# cs301_group7.net
KiCad netlist of a schematic drawn in Altium Designer
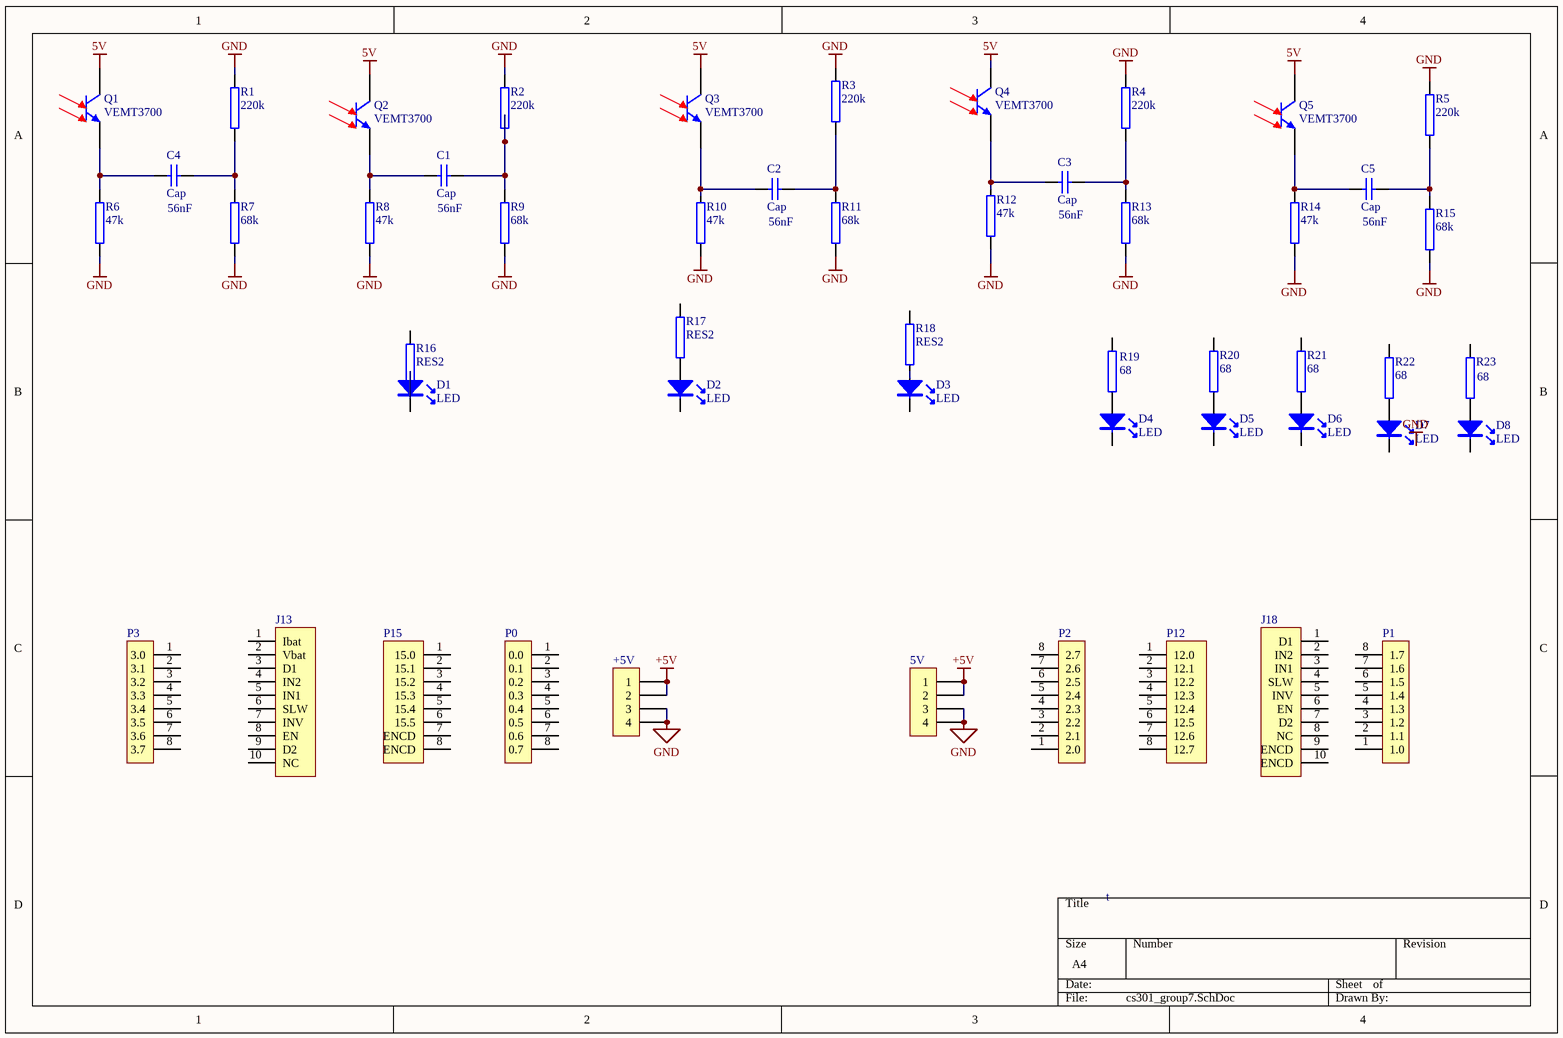
[diagram p0: cs301_group7.SchDoc]

(export (version "E")
  (design (tool "Eeschema 10.0.6"))
  (components
    (comp (ref "+5V")
      (value "5V")
      (footprint "IDC4")
      (description "Connector")
      (libsource (lib "Miscellaneous Devices") (part "CON4"))
    )
    (comp (ref "5V")
      (value "5V")
      (footprint "IDC4")
      (description "Connector")
      (libsource (lib "Miscellaneous Devices") (part "CON4"))
    )
    (comp (ref "C1")
      (value "Cap")
      (footprint "RAD-0.3")
      (description "Capacitor")
      (fields (field (name "ALTIUM_VALUE") "56nF") (field (name "PUBLISHER") "Altium Limited"))
      (libsource (lib "Miscellaneous Devices") (part "Cap"))
    )
    (comp (ref "C2")
      (value "Cap")
      (footprint "RAD-0.3")
      (description "Capacitor")
      (fields (field (name "ALTIUM_VALUE") "56nF") (field (name "PUBLISHER") "Altium Limited"))
      (libsource (lib "Miscellaneous Devices") (part "Cap"))
    )
    (comp (ref "C3")
      (value "Cap")
      (footprint "RAD-0.3")
      (description "Capacitor")
      (fields (field (name "ALTIUM_VALUE") "56nF") (field (name "PUBLISHER") "Altium Limited"))
      (libsource (lib "Miscellaneous Devices") (part "Cap"))
    )
    (comp (ref "C4")
      (value "Cap")
      (footprint "RAD-0.3")
      (description "Capacitor")
      (fields (field (name "ALTIUM_VALUE") "56nF") (field (name "PUBLISHER") "Altium Limited"))
      (libsource (lib "Miscellaneous Devices") (part "Cap"))
    )
    (comp (ref "C5")
      (value "Cap")
      (footprint "RAD-0.3")
      (description "Capacitor")
      (fields (field (name "ALTIUM_VALUE") "56nF") (field (name "PUBLISHER") "Altium Limited"))
      (libsource (lib "Miscellaneous Devices") (part "Cap"))
    )
    (comp (ref "D1") (value "LED") (footprint "LED0.1/5MM") (libsource (lib "COMSYS301_2013") (part "LED")))
    (comp (ref "D2") (value "LED") (footprint "LED0.1/5MM") (libsource (lib "COMSYS301_2013") (part "LED")))
    (comp (ref "D3") (value "LED") (footprint "LED0.1/5MM") (libsource (lib "COMSYS301_2013") (part "LED")))
    (comp (ref "D4") (value "LED") (footprint "LED0.1/5MM") (libsource (lib "COMSYS301_2013") (part "LED")))
    (comp (ref "D5") (value "LED") (footprint "LED0.1/5MM") (libsource (lib "COMSYS301_2013") (part "LED")))
    (comp (ref "D6") (value "LED") (footprint "LED0.1/5MM") (libsource (lib "COMSYS301_2013") (part "LED")))
    (comp (ref "D7") (value "LED") (footprint "LED0.1/5MM") (libsource (lib "COMSYS301_2013") (part "LED")))
    (comp (ref "D8") (value "LED") (footprint "LED0.1/5MM") (libsource (lib "COMSYS301_2013") (part "LED")))
    (comp (ref "J13")
      (value "CON10")
      (footprint "idc10")
      (description "Connector")
      (libsource (lib "") (part "CON10_1"))
    )
    (comp (ref "J18")
      (value "CON10")
      (footprint "IDC10")
      (description "Connector")
      (libsource (lib "Miscellaneous Devices") (part "CON10"))
    )
    (comp (ref "P0")
      (value "P0")
      (footprint "idc8")
      (description "Connector")
      (libsource (lib "Miscellaneous Devices") (part "CON8"))
    )
    (comp (ref "P1")
      (value "P1")
      (footprint "idc8")
      (description "Connector")
      (libsource (lib "") (part "CON8_1"))
    )
    (comp (ref "P2")
      (value "P2")
      (footprint "idc8")
      (description "Connector")
      (libsource (lib "") (part "CON8_2"))
    )
    (comp (ref "P3")
      (value "P3")
      (footprint "idc8")
      (description "Connector")
      (libsource (lib "Miscellaneous Devices") (part "CON8"))
    )
    (comp (ref "P12")
      (value "P12")
      (footprint "idc8")
      (description "Connector")
      (libsource (lib "Miscellaneous Devices") (part "CON8_1"))
    )
    (comp (ref "P15")
      (value "P15")
      (footprint "idc8")
      (description "Connector")
      (libsource (lib "") (part "CON8_1_1"))
    )
    (comp (ref "Q1")
      (value "VEMT3700")
      (footprint "VEMT3700")
      (description "Silicon NPN Phototransistor")
      (libsource (lib "COMSYS301_2013") (part "VEMT3700"))
    )
    (comp (ref "Q2")
      (value "VEMT3700")
      (footprint "VEMT3700")
      (description "Silicon NPN Phototransistor")
      (libsource (lib "COMSYS301_2013") (part "VEMT3700"))
    )
    (comp (ref "Q3")
      (value "VEMT3700")
      (footprint "VEMT3700")
      (description "Silicon NPN Phototransistor")
      (libsource (lib "COMSYS301_2013") (part "VEMT3700"))
    )
    (comp (ref "Q4")
      (value "VEMT3700")
      (footprint "VEMT3700")
      (description "Silicon NPN Phototransistor")
      (libsource (lib "COMSYS301_2013") (part "VEMT3700"))
    )
    (comp (ref "Q5")
      (value "VEMT3700")
      (footprint "VEMT3700")
      (description "Silicon NPN Phototransistor")
      (libsource (lib "COMSYS301_2013") (part "VEMT3700"))
    )
    (comp (ref "R1") (value "220k") (footprint "AXIAL0.4") (libsource (lib "COMSYS301_2013") (part "RES2")))
    (comp (ref "R2") (value "220k") (footprint "AXIAL0.4") (libsource (lib "COMSYS301_2013") (part "RES2")))
    (comp (ref "R3") (value "220k") (footprint "AXIAL0.4") (libsource (lib "COMSYS301_2013") (part "RES2")))
    (comp (ref "R4") (value "220k") (footprint "AXIAL0.4") (libsource (lib "COMSYS301_2013") (part "RES2")))
    (comp (ref "R5") (value "220k") (footprint "AXIAL0.4") (libsource (lib "COMSYS301_2013") (part "RES2")))
    (comp (ref "R6") (value "47k") (footprint "AXIAL0.4") (libsource (lib "COMSYS301_2013") (part "RES2")))
    (comp (ref "R7") (value "68k") (footprint "AXIAL0.4") (libsource (lib "COMSYS301_2013") (part "RES2")))
    (comp (ref "R8") (value "47k") (footprint "AXIAL0.4") (libsource (lib "COMSYS301_2013") (part "RES2")))
    (comp (ref "R9") (value "68k") (footprint "AXIAL0.4") (libsource (lib "COMSYS301_2013") (part "RES2")))
    (comp (ref "R10") (value "47k") (footprint "AXIAL0.4") (libsource (lib "COMSYS301_2013") (part "RES2")))
    (comp (ref "R11") (value "68k") (footprint "AXIAL0.4") (libsource (lib "COMSYS301_2013") (part "RES2")))
    (comp (ref "R12") (value "47k") (footprint "AXIAL0.4") (libsource (lib "COMSYS301_2013") (part "RES2")))
    (comp (ref "R13") (value "68k") (footprint "AXIAL0.4") (libsource (lib "COMSYS301_2013") (part "RES2")))
    (comp (ref "R14") (value "47k") (footprint "AXIAL0.4") (libsource (lib "COMSYS301_2013") (part "RES2")))
    (comp (ref "R15") (value "68k") (footprint "AXIAL0.4") (libsource (lib "COMSYS301_2013") (part "RES2")))
    (comp (ref "R16") (value "RES2") (footprint "AXIAL0.4") (libsource (lib "COMSYS301_2013") (part "RES2")))
    (comp (ref "R17") (value "RES2") (footprint "AXIAL0.4") (libsource (lib "COMSYS301_2013") (part "RES2")))
    (comp (ref "R18") (value "RES2") (footprint "AXIAL0.4") (libsource (lib "COMSYS301_2013") (part "RES2")))
    (comp (ref "R19") (value "68") (footprint "AXIAL0.4") (libsource (lib "COMSYS301_2013") (part "RES2")))
    (comp (ref "R20") (value "68") (footprint "AXIAL0.4") (libsource (lib "COMSYS301_2013") (part "RES2")))
    (comp (ref "R21") (value "68") (footprint "AXIAL0.4") (libsource (lib "COMSYS301_2013") (part "RES2")))
    (comp (ref "R22") (value "68") (footprint "AXIAL0.4") (libsource (lib "COMSYS301_2013") (part "RES2")))
    (comp (ref "R23") (value "68") (footprint "AXIAL0.4") (libsource (lib "COMSYS301_2013") (part "RES2")))
  )
  (nets
    (net (code "1") (name "+5V") (class "Default")
      (node (ref "+5V") (pin "1") (pinfunction "1_1") (pintype "passive"))
      (node (ref "+5V") (pin "2") (pinfunction "2_2") (pintype "passive"))
      (node (ref "5V") (pin "1") (pinfunction "1_1") (pintype "passive"))
      (node (ref "5V") (pin "2") (pinfunction "2_2") (pintype "passive"))
    )
    (net (code "2") (name "5V") (class "Default")
      (node (ref "Q1") (pin "1") (pinfunction "C_1") (pintype "passive"))
      (node (ref "Q2") (pin "1") (pinfunction "C_1") (pintype "passive"))
      (node (ref "Q3") (pin "1") (pinfunction "C_1") (pintype "passive"))
      (node (ref "Q4") (pin "1") (pinfunction "C_1") (pintype "passive"))
      (node (ref "Q5") (pin "1") (pinfunction "C_1") (pintype "passive"))
    )
    (net (code "3") (name "GND") (class "Default")
      (node (ref "+5V") (pin "3") (pinfunction "3_3") (pintype "passive"))
      (node (ref "+5V") (pin "4") (pinfunction "4_4") (pintype "passive"))
      (node (ref "5V") (pin "3") (pinfunction "3_3") (pintype "passive"))
      (node (ref "5V") (pin "4") (pinfunction "4_4") (pintype "passive"))
      (node (ref "R1") (pin "2") (pinfunction "2_2") (pintype "passive"))
      (node (ref "R10") (pin "1") (pinfunction "1_1") (pintype "passive"))
      (node (ref "R11") (pin "1") (pinfunction "1_1") (pintype "passive"))
      (node (ref "R12") (pin "1") (pinfunction "1_1") (pintype "passive"))
      (node (ref "R13") (pin "1") (pinfunction "1_1") (pintype "passive"))
      (node (ref "R14") (pin "1") (pinfunction "1_1") (pintype "passive"))
      (node (ref "R15") (pin "1") (pinfunction "1_1") (pintype "passive"))
      (node (ref "R2") (pin "2") (pinfunction "2_2") (pintype "passive"))
      (node (ref "R3") (pin "2") (pinfunction "2_2") (pintype "passive"))
      (node (ref "R4") (pin "2") (pinfunction "2_2") (pintype "passive"))
      (node (ref "R5") (pin "2") (pinfunction "2_2") (pintype "passive"))
      (node (ref "R6") (pin "1") (pinfunction "1_1") (pintype "passive"))
      (node (ref "R7") (pin "1") (pinfunction "1_1") (pintype "passive"))
      (node (ref "R8") (pin "1") (pinfunction "1_1") (pintype "passive"))
      (node (ref "R9") (pin "1") (pinfunction "1_1") (pintype "passive"))
    )
    (net (code "4") (name "Net-(C1-Pad2)") (class "Default")
      (node (ref "C1") (pin "2") (pinfunction "2_2") (pintype "passive"))
      (node (ref "R2") (pin "1") (pinfunction "1_1") (pintype "passive"))
      (node (ref "R9") (pin "2") (pinfunction "2_2") (pintype "passive"))
    )
    (net (code "5") (name "Net-(C2-Pad2)") (class "Default")
      (node (ref "C2") (pin "2") (pinfunction "2_2") (pintype "passive"))
      (node (ref "R11") (pin "2") (pinfunction "2_2") (pintype "passive"))
      (node (ref "R3") (pin "1") (pinfunction "1_1") (pintype "passive"))
    )
    (net (code "6") (name "Net-(C3-Pad2)") (class "Default")
      (node (ref "C3") (pin "2") (pinfunction "2_2") (pintype "passive"))
      (node (ref "R13") (pin "2") (pinfunction "2_2") (pintype "passive"))
      (node (ref "R4") (pin "1") (pinfunction "1_1") (pintype "passive"))
    )
    (net (code "7") (name "Net-(C4-Pad2)") (class "Default")
      (node (ref "C4") (pin "2") (pinfunction "2_2") (pintype "passive"))
      (node (ref "R1") (pin "1") (pinfunction "1_1") (pintype "passive"))
      (node (ref "R7") (pin "2") (pinfunction "2_2") (pintype "passive"))
    )
    (net (code "8") (name "Net-(C5-Pad2)") (class "Default")
      (node (ref "C5") (pin "2") (pinfunction "2_2") (pintype "passive"))
      (node (ref "R15") (pin "2") (pinfunction "2_2") (pintype "passive"))
      (node (ref "R5") (pin "1") (pinfunction "1_1") (pintype "passive"))
    )
    (net (code "9") (name "Net-(D1-1)") (class "Default")
      (node (ref "D1") (pin "A") (pinfunction "1_A") (pintype "passive"))
      (node (ref "R16") (pin "1") (pinfunction "1_1") (pintype "passive"))
    )
    (net (code "10") (name "Net-(D2-1)") (class "Default")
      (node (ref "D2") (pin "A") (pinfunction "1_A") (pintype "passive"))
      (node (ref "R17") (pin "1") (pinfunction "1_1") (pintype "passive"))
    )
    (net (code "11") (name "Net-(D3-1)") (class "Default")
      (node (ref "D3") (pin "A") (pinfunction "1_A") (pintype "passive"))
      (node (ref "R18") (pin "2") (pinfunction "2_2") (pintype "passive"))
    )
    (net (code "12") (name "Net-(D4-1)") (class "Default")
      (node (ref "D4") (pin "A") (pinfunction "1_A") (pintype "passive"))
      (node (ref "R19") (pin "1") (pinfunction "1_1") (pintype "passive"))
    )
    (net (code "13") (name "Net-(D5-1)") (class "Default")
      (node (ref "D5") (pin "A") (pinfunction "1_A") (pintype "passive"))
      (node (ref "R20") (pin "1") (pinfunction "1_1") (pintype "passive"))
    )
    (net (code "14") (name "Net-(D6-1)") (class "Default")
      (node (ref "D6") (pin "A") (pinfunction "1_A") (pintype "passive"))
      (node (ref "R21") (pin "1") (pinfunction "1_1") (pintype "passive"))
    )
    (net (code "15") (name "Net-(D7-1)") (class "Default")
      (node (ref "D7") (pin "A") (pinfunction "1_A") (pintype "passive"))
      (node (ref "R22") (pin "1") (pinfunction "1_1") (pintype "passive"))
    )
    (net (code "16") (name "Net-(D8-1)") (class "Default")
      (node (ref "D8") (pin "A") (pinfunction "1_A") (pintype "passive"))
      (node (ref "R23") (pin "1") (pinfunction "1_1") (pintype "passive"))
    )
    (net (code "17") (name "Net-(Q1-E)") (class "Default")
      (node (ref "C4") (pin "1") (pinfunction "1_1") (pintype "passive"))
      (node (ref "Q1") (pin "2") (pinfunction "E_2") (pintype "passive"))
      (node (ref "R6") (pin "2") (pinfunction "2_2") (pintype "passive"))
    )
    (net (code "18") (name "Net-(Q2-E)") (class "Default")
      (node (ref "C1") (pin "1") (pinfunction "1_1") (pintype "passive"))
      (node (ref "Q2") (pin "2") (pinfunction "E_2") (pintype "passive"))
      (node (ref "R8") (pin "2") (pinfunction "2_2") (pintype "passive"))
    )
    (net (code "19") (name "Net-(Q3-E)") (class "Default")
      (node (ref "C2") (pin "1") (pinfunction "1_1") (pintype "passive"))
      (node (ref "Q3") (pin "2") (pinfunction "E_2") (pintype "passive"))
      (node (ref "R10") (pin "2") (pinfunction "2_2") (pintype "passive"))
    )
    (net (code "20") (name "Net-(Q4-E)") (class "Default")
      (node (ref "C3") (pin "1") (pinfunction "1_1") (pintype "passive"))
      (node (ref "Q4") (pin "2") (pinfunction "E_2") (pintype "passive"))
      (node (ref "R12") (pin "2") (pinfunction "2_2") (pintype "passive"))
    )
    (net (code "21") (name "Net-(Q5-E)") (class "Default")
      (node (ref "C5") (pin "1") (pinfunction "1_1") (pintype "passive"))
      (node (ref "Q5") (pin "2") (pinfunction "E_2") (pintype "passive"))
      (node (ref "R14") (pin "2") (pinfunction "2_2") (pintype "passive"))
    )
    (net (code "22") (name "unconnected-(D1-2-PadK)") (class "Default")
      (node (ref "D1") (pin "K") (pinfunction "2_K") (pintype "passive"))
    )
    (net (code "23") (name "unconnected-(D2-2-PadK)") (class "Default")
      (node (ref "D2") (pin "K") (pinfunction "2_K") (pintype "passive"))
    )
    (net (code "24") (name "unconnected-(D3-2-PadK)") (class "Default")
      (node (ref "D3") (pin "K") (pinfunction "2_K") (pintype "passive"))
    )
    (net (code "25") (name "unconnected-(D4-2-PadK)") (class "Default")
      (node (ref "D4") (pin "K") (pinfunction "2_K") (pintype "passive"))
    )
    (net (code "26") (name "unconnected-(D5-2-PadK)") (class "Default")
      (node (ref "D5") (pin "K") (pinfunction "2_K") (pintype "passive"))
    )
    (net (code "27") (name "unconnected-(D6-2-PadK)") (class "Default")
      (node (ref "D6") (pin "K") (pinfunction "2_K") (pintype "passive"))
    )
    (net (code "28") (name "unconnected-(D7-2-PadK)") (class "Default")
      (node (ref "D7") (pin "K") (pinfunction "2_K") (pintype "passive"))
    )
    (net (code "29") (name "unconnected-(D8-2-PadK)") (class "Default")
      (node (ref "D8") (pin "K") (pinfunction "2_K") (pintype "passive"))
    )
    (net (code "30") (name "unconnected-(J13-D1-Pad3)") (class "Default")
      (node (ref "J13") (pin "3") (pinfunction "D1_3") (pintype "passive"))
    )
    (net (code "31") (name "unconnected-(J13-D2-Pad9)") (class "Default")
      (node (ref "J13") (pin "9") (pinfunction "D2_9") (pintype "passive"))
    )
    (net (code "32") (name "unconnected-(J13-EN-Pad8)") (class "Default")
      (node (ref "J13") (pin "8") (pinfunction "EN_8") (pintype "passive"))
    )
    (net (code "33") (name "unconnected-(J13-IN1-Pad5)") (class "Default")
      (node (ref "J13") (pin "5") (pinfunction "IN1_5") (pintype "passive"))
    )
    (net (code "34") (name "unconnected-(J13-IN2-Pad4)") (class "Default")
      (node (ref "J13") (pin "4") (pinfunction "IN2_4") (pintype "passive"))
    )
    (net (code "35") (name "unconnected-(J13-INV-Pad7)") (class "Default")
      (node (ref "J13") (pin "7") (pinfunction "INV_7") (pintype "passive"))
    )
    (net (code "36") (name "unconnected-(J13-Ibat-Pad1)") (class "Default")
      (node (ref "J13") (pin "1") (pinfunction "Ibat_1") (pintype "passive"))
    )
    (net (code "37") (name "unconnected-(J13-NC-Pad10)") (class "Default")
      (node (ref "J13") (pin "10") (pinfunction "NC_10") (pintype "passive"))
    )
    (net (code "38") (name "unconnected-(J13-SLW-Pad6)") (class "Default")
      (node (ref "J13") (pin "6") (pinfunction "SLW_6") (pintype "passive"))
    )
    (net (code "39") (name "unconnected-(J13-Vbat-Pad2)") (class "Default")
      (node (ref "J13") (pin "2") (pinfunction "Vbat_2") (pintype "passive"))
    )
    (net (code "40") (name "unconnected-(J18-D1-Pad1)") (class "Default")
      (node (ref "J18") (pin "1") (pinfunction "D1_1") (pintype "passive"))
    )
    (net (code "41") (name "unconnected-(J18-D2-Pad7)") (class "Default")
      (node (ref "J18") (pin "7") (pinfunction "D2_7") (pintype "passive"))
    )
    (net (code "42") (name "unconnected-(J18-EN-Pad6)") (class "Default")
      (node (ref "J18") (pin "6") (pinfunction "EN_6") (pintype "passive"))
    )
    (net (code "43") (name "unconnected-(J18-ENCD-Pad9)") (class "Default")
      (node (ref "J18") (pin "9") (pinfunction "ENCD_9") (pintype "passive"))
    )
    (net (code "44") (name "unconnected-(J18-ENCD-Pad10)") (class "Default")
      (node (ref "J18") (pin "10") (pinfunction "ENCD_10") (pintype "passive"))
    )
    (net (code "45") (name "unconnected-(J18-IN1-Pad3)") (class "Default")
      (node (ref "J18") (pin "3") (pinfunction "IN1_3") (pintype "passive"))
    )
    (net (code "46") (name "unconnected-(J18-IN2-Pad2)") (class "Default")
      (node (ref "J18") (pin "2") (pinfunction "IN2_2") (pintype "passive"))
    )
    (net (code "47") (name "unconnected-(J18-INV-Pad5)") (class "Default")
      (node (ref "J18") (pin "5") (pinfunction "INV_5") (pintype "passive"))
    )
    (net (code "48") (name "unconnected-(J18-NC-Pad8)") (class "Default")
      (node (ref "J18") (pin "8") (pinfunction "NC_8") (pintype "passive"))
    )
    (net (code "49") (name "unconnected-(J18-SLW-Pad4)") (class "Default")
      (node (ref "J18") (pin "4") (pinfunction "SLW_4") (pintype "passive"))
    )
    (net (code "50") (name "unconnected-(P0-3.0-Pad1)") (class "Default")
      (node (ref "P0") (pin "1") (pinfunction "3.0_1") (pintype "passive"))
    )
    (net (code "51") (name "unconnected-(P0-3.1-Pad2)") (class "Default")
      (node (ref "P0") (pin "2") (pinfunction "3.1_2") (pintype "passive"))
    )
    (net (code "52") (name "unconnected-(P0-3.2-Pad3)") (class "Default")
      (node (ref "P0") (pin "3") (pinfunction "3.2_3") (pintype "passive"))
    )
    (net (code "53") (name "unconnected-(P0-3.3-Pad4)") (class "Default")
      (node (ref "P0") (pin "4") (pinfunction "3.3_4") (pintype "passive"))
    )
    (net (code "54") (name "unconnected-(P0-3.4-Pad5)") (class "Default")
      (node (ref "P0") (pin "5") (pinfunction "3.4_5") (pintype "passive"))
    )
    (net (code "55") (name "unconnected-(P0-3.5-Pad6)") (class "Default")
      (node (ref "P0") (pin "6") (pinfunction "3.5_6") (pintype "passive"))
    )
    (net (code "56") (name "unconnected-(P0-3.6-Pad7)") (class "Default")
      (node (ref "P0") (pin "7") (pinfunction "3.6_7") (pintype "passive"))
    )
    (net (code "57") (name "unconnected-(P0-3.7-Pad8)") (class "Default")
      (node (ref "P0") (pin "8") (pinfunction "3.7_8") (pintype "passive"))
    )
    (net (code "58") (name "unconnected-(P1-1.0-Pad1)") (class "Default")
      (node (ref "P1") (pin "1") (pinfunction "1.0_1") (pintype "passive"))
    )
    (net (code "59") (name "unconnected-(P1-1.1-Pad2)") (class "Default")
      (node (ref "P1") (pin "2") (pinfunction "1.1_2") (pintype "passive"))
    )
    (net (code "60") (name "unconnected-(P1-1.2-Pad3)") (class "Default")
      (node (ref "P1") (pin "3") (pinfunction "1.2_3") (pintype "passive"))
    )
    (net (code "61") (name "unconnected-(P1-1.3-Pad4)") (class "Default")
      (node (ref "P1") (pin "4") (pinfunction "1.3_4") (pintype "passive"))
    )
    (net (code "62") (name "unconnected-(P1-1.4-Pad5)") (class "Default")
      (node (ref "P1") (pin "5") (pinfunction "1.4_5") (pintype "passive"))
    )
    (net (code "63") (name "unconnected-(P1-1.5-Pad6)") (class "Default")
      (node (ref "P1") (pin "6") (pinfunction "1.5_6") (pintype "passive"))
    )
    (net (code "64") (name "unconnected-(P1-1.6-Pad7)") (class "Default")
      (node (ref "P1") (pin "7") (pinfunction "1.6_7") (pintype "passive"))
    )
    (net (code "65") (name "unconnected-(P1-1.7-Pad8)") (class "Default")
      (node (ref "P1") (pin "8") (pinfunction "1.7_8") (pintype "passive"))
    )
    (net (code "66") (name "unconnected-(P2-2.0-Pad1)") (class "Default")
      (node (ref "P2") (pin "1") (pinfunction "2.0_1") (pintype "passive"))
    )
    (net (code "67") (name "unconnected-(P2-2.1-Pad2)") (class "Default")
      (node (ref "P2") (pin "2") (pinfunction "2.1_2") (pintype "passive"))
    )
    (net (code "68") (name "unconnected-(P2-2.2-Pad3)") (class "Default")
      (node (ref "P2") (pin "3") (pinfunction "2.2_3") (pintype "passive"))
    )
    (net (code "69") (name "unconnected-(P2-2.3-Pad4)") (class "Default")
      (node (ref "P2") (pin "4") (pinfunction "2.3_4") (pintype "passive"))
    )
    (net (code "70") (name "unconnected-(P2-2.4-Pad5)") (class "Default")
      (node (ref "P2") (pin "5") (pinfunction "2.4_5") (pintype "passive"))
    )
    (net (code "71") (name "unconnected-(P2-2.5-Pad6)") (class "Default")
      (node (ref "P2") (pin "6") (pinfunction "2.5_6") (pintype "passive"))
    )
    (net (code "72") (name "unconnected-(P2-2.6-Pad7)") (class "Default")
      (node (ref "P2") (pin "7") (pinfunction "2.6_7") (pintype "passive"))
    )
    (net (code "73") (name "unconnected-(P2-2.7-Pad8)") (class "Default")
      (node (ref "P2") (pin "8") (pinfunction "2.7_8") (pintype "passive"))
    )
    (net (code "74") (name "unconnected-(P3-3.0-Pad1)") (class "Default")
      (node (ref "P3") (pin "1") (pinfunction "3.0_1") (pintype "passive"))
    )
    (net (code "75") (name "unconnected-(P3-3.1-Pad2)") (class "Default")
      (node (ref "P3") (pin "2") (pinfunction "3.1_2") (pintype "passive"))
    )
    (net (code "76") (name "unconnected-(P3-3.2-Pad3)") (class "Default")
      (node (ref "P3") (pin "3") (pinfunction "3.2_3") (pintype "passive"))
    )
    (net (code "77") (name "unconnected-(P3-3.3-Pad4)") (class "Default")
      (node (ref "P3") (pin "4") (pinfunction "3.3_4") (pintype "passive"))
    )
    (net (code "78") (name "unconnected-(P3-3.4-Pad5)") (class "Default")
      (node (ref "P3") (pin "5") (pinfunction "3.4_5") (pintype "passive"))
    )
    (net (code "79") (name "unconnected-(P3-3.5-Pad6)") (class "Default")
      (node (ref "P3") (pin "6") (pinfunction "3.5_6") (pintype "passive"))
    )
    (net (code "80") (name "unconnected-(P3-3.6-Pad7)") (class "Default")
      (node (ref "P3") (pin "7") (pinfunction "3.6_7") (pintype "passive"))
    )
    (net (code "81") (name "unconnected-(P3-3.7-Pad8)") (class "Default")
      (node (ref "P3") (pin "8") (pinfunction "3.7_8") (pintype "passive"))
    )
    (net (code "82") (name "unconnected-(P12-12.0-Pad1)") (class "Default")
      (node (ref "P12") (pin "1") (pinfunction "12.0_1") (pintype "passive"))
    )
    (net (code "83") (name "unconnected-(P12-12.1-Pad2)") (class "Default")
      (node (ref "P12") (pin "2") (pinfunction "12.1_2") (pintype "passive"))
    )
    (net (code "84") (name "unconnected-(P12-12.2-Pad3)") (class "Default")
      (node (ref "P12") (pin "3") (pinfunction "12.2_3") (pintype "passive"))
    )
    (net (code "85") (name "unconnected-(P12-12.3-Pad4)") (class "Default")
      (node (ref "P12") (pin "4") (pinfunction "12.3_4") (pintype "passive"))
    )
    (net (code "86") (name "unconnected-(P12-12.4-Pad5)") (class "Default")
      (node (ref "P12") (pin "5") (pinfunction "12.4_5") (pintype "passive"))
    )
    (net (code "87") (name "unconnected-(P12-12.5-Pad6)") (class "Default")
      (node (ref "P12") (pin "6") (pinfunction "12.5_6") (pintype "passive"))
    )
    (net (code "88") (name "unconnected-(P12-12.6-Pad7)") (class "Default")
      (node (ref "P12") (pin "7") (pinfunction "12.6_7") (pintype "passive"))
    )
    (net (code "89") (name "unconnected-(P12-12.7-Pad8)") (class "Default")
      (node (ref "P12") (pin "8") (pinfunction "12.7_8") (pintype "passive"))
    )
    (net (code "90") (name "unconnected-(P15-15.0-Pad1)") (class "Default")
      (node (ref "P15") (pin "1") (pinfunction "15.0_1") (pintype "passive"))
    )
    (net (code "91") (name "unconnected-(P15-15.1-Pad2)") (class "Default")
      (node (ref "P15") (pin "2") (pinfunction "15.1_2") (pintype "passive"))
    )
    (net (code "92") (name "unconnected-(P15-15.2-Pad3)") (class "Default")
      (node (ref "P15") (pin "3") (pinfunction "15.2_3") (pintype "passive"))
    )
    (net (code "93") (name "unconnected-(P15-15.3-Pad4)") (class "Default")
      (node (ref "P15") (pin "4") (pinfunction "15.3_4") (pintype "passive"))
    )
    (net (code "94") (name "unconnected-(P15-15.4-Pad5)") (class "Default")
      (node (ref "P15") (pin "5") (pinfunction "15.4_5") (pintype "passive"))
    )
    (net (code "95") (name "unconnected-(P15-15.5-Pad6)") (class "Default")
      (node (ref "P15") (pin "6") (pinfunction "15.5_6") (pintype "passive"))
    )
    (net (code "96") (name "unconnected-(P15-ENCD-Pad7)") (class "Default")
      (node (ref "P15") (pin "7") (pinfunction "ENCD_7") (pintype "passive"))
    )
    (net (code "97") (name "unconnected-(P15-ENCD-Pad8)") (class "Default")
      (node (ref "P15") (pin "8") (pinfunction "ENCD_8") (pintype "passive"))
    )
    (net (code "98") (name "unconnected-(R16-Pad2)") (class "Default")
      (node (ref "R16") (pin "2") (pinfunction "2_2") (pintype "passive"))
    )
    (net (code "99") (name "unconnected-(R17-Pad2)") (class "Default")
      (node (ref "R17") (pin "2") (pinfunction "2_2") (pintype "passive"))
    )
    (net (code "100") (name "unconnected-(R18-Pad1)") (class "Default")
      (node (ref "R18") (pin "1") (pinfunction "1_1") (pintype "passive"))
    )
    (net (code "101") (name "unconnected-(R19-Pad2)") (class "Default")
      (node (ref "R19") (pin "2") (pinfunction "2_2") (pintype "passive"))
    )
    (net (code "102") (name "unconnected-(R20-Pad2)") (class "Default")
      (node (ref "R20") (pin "2") (pinfunction "2_2") (pintype "passive"))
    )
    (net (code "103") (name "unconnected-(R21-Pad2)") (class "Default")
      (node (ref "R21") (pin "2") (pinfunction "2_2") (pintype "passive"))
    )
    (net (code "104") (name "unconnected-(R22-Pad2)") (class "Default")
      (node (ref "R22") (pin "2") (pinfunction "2_2") (pintype "passive"))
    )
    (net (code "105") (name "unconnected-(R23-Pad2)") (class "Default")
      (node (ref "R23") (pin "2") (pinfunction "2_2") (pintype "passive"))
    )
  )
)
